# 1_PowerSupply.net
KiCad netlist of a schematic drawn in Altium Designer
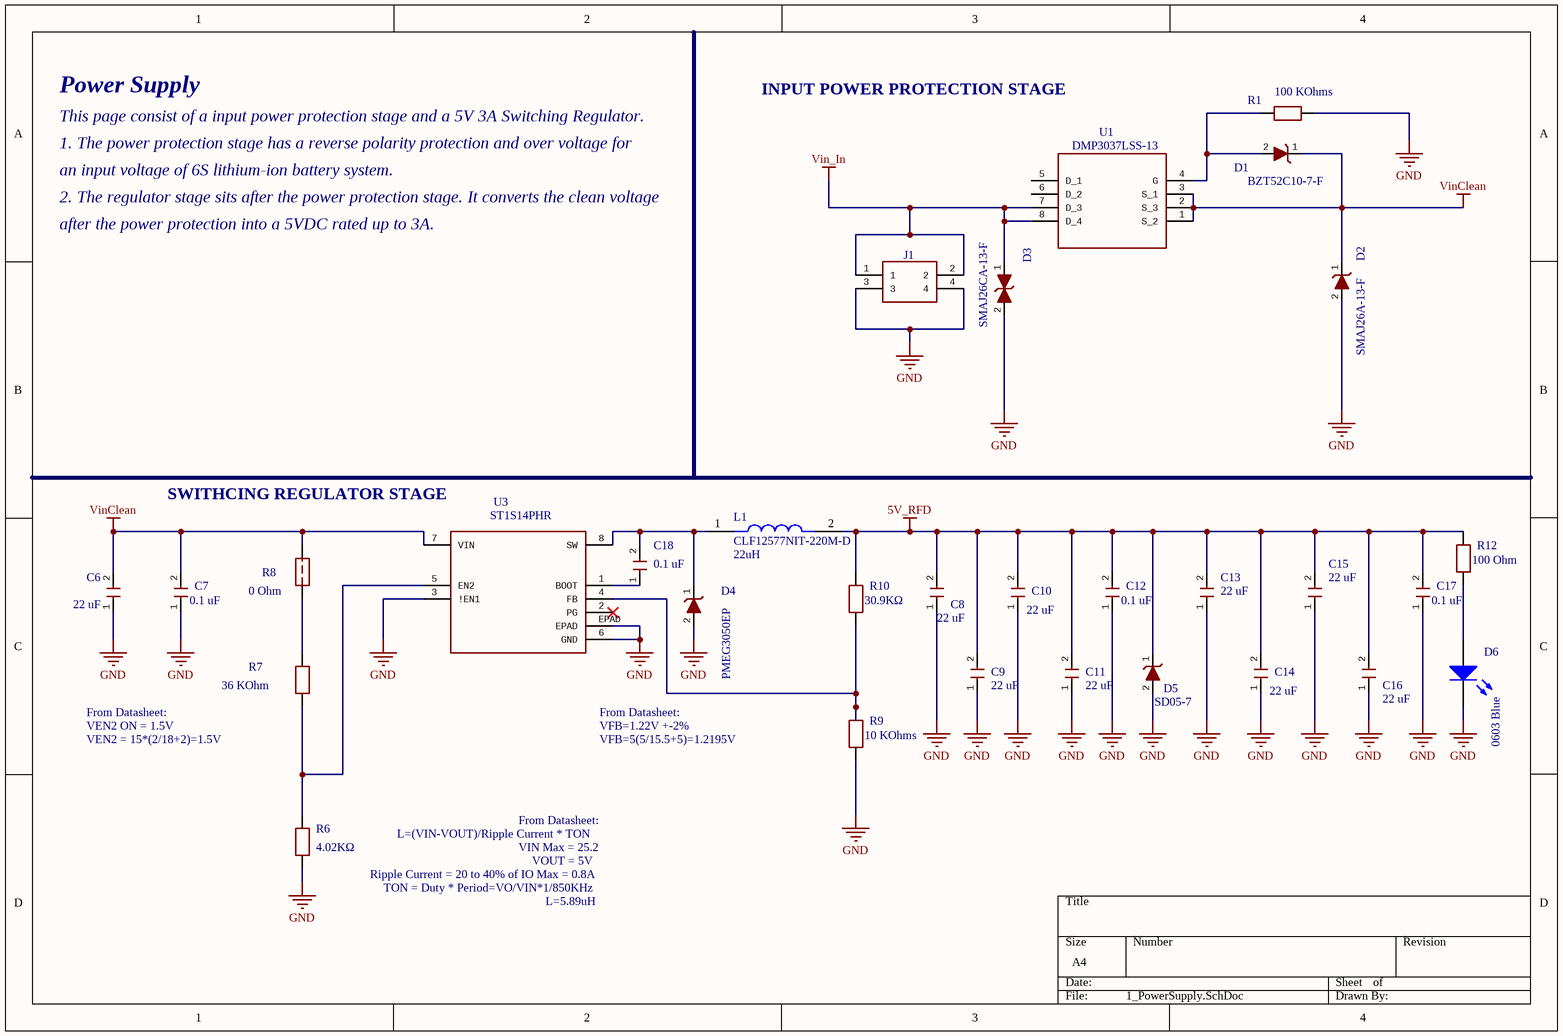
[diagram p0: 1_PowerSupply.SchDoc]

(export (version "E")
  (design (tool "Eeschema 10.0.6"))
  (components
    (comp (ref "C6")
      (value "22 uF")
      (footprint "CAP_0805")
      (description "Cap Ceramic 22uF 50V 0805")
      (fields (field (name "MANUFACTURER_PART_NUMBER") "C2012X5R1V226MT000E"))
      (libsource (lib "Passives") (part "C2012X5R1V226MT000E"))
    )
    (comp (ref "C7")
      (value "0.1 uF")
      (footprint "CAP_0603")
      (description "Cap Ceramic 0.1uF 50V 0603")
      (fields (field (name "PARTNUMBER") "CL10B104KB8NNNC"))
      (libsource (lib "Passives") (part "CL10B104KB8NNNC"))
    )
    (comp (ref "C8")
      (value "22 uF")
      (footprint "CAP_0805")
      (description "Cap Ceramic 22uF 50V 0805")
      (fields (field (name "MANUFACTURER_PART_NUMBER") "C2012X5R1V226MT000E"))
      (libsource (lib "Passives") (part "C2012X5R1V226MT000E"))
    )
    (comp (ref "C9")
      (value "22 uF")
      (footprint "CAP_0805")
      (description "Cap Ceramic 22uF 50V 0805")
      (fields (field (name "MANUFACTURER_PART_NUMBER") "C2012X5R1V226MT000E"))
      (libsource (lib "Passives") (part "C2012X5R1V226MT000E"))
    )
    (comp (ref "C10")
      (value "22 uF")
      (footprint "CAP_0805")
      (description "Cap Ceramic 22uF 50V 0805")
      (fields (field (name "MANUFACTURER_PART_NUMBER") "C2012X5R1V226MT000E"))
      (libsource (lib "Passives") (part "C2012X5R1V226MT000E"))
    )
    (comp (ref "C11")
      (value "22 uF")
      (footprint "CAP_0805")
      (description "Cap Ceramic 22uF 50V 0805")
      (fields (field (name "MANUFACTURER_PART_NUMBER") "C2012X5R1V226MT000E"))
      (libsource (lib "Passives") (part "C2012X5R1V226MT000E"))
    )
    (comp (ref "C12")
      (value "0.1 uF")
      (footprint "CAP_0603")
      (description "Cap Ceramic 0.1uF 50V 0603")
      (fields (field (name "PARTNUMBER") "CL10B104KB8NNNC"))
      (libsource (lib "Passives") (part "CL10B104KB8NNNC"))
    )
    (comp (ref "C13")
      (value "22 uF")
      (footprint "CAP_0805")
      (description "Cap Ceramic 22uF 50V 0805")
      (fields (field (name "MANUFACTURER_PART_NUMBER") "C2012X5R1V226MT000E"))
      (libsource (lib "Passives") (part "C2012X5R1V226MT000E"))
    )
    (comp (ref "C14")
      (value "22 uF")
      (footprint "CAP_0805")
      (description "Cap Ceramic 22uF 50V 0805")
      (fields (field (name "MANUFACTURER_PART_NUMBER") "C2012X5R1V226MT000E"))
      (libsource (lib "Passives") (part "C2012X5R1V226MT000E"))
    )
    (comp (ref "C15")
      (value "22 uF")
      (footprint "CAP_0805")
      (description "Cap Ceramic 22uF 50V 0805")
      (fields (field (name "MANUFACTURER_PART_NUMBER") "C2012X5R1V226MT000E"))
      (libsource (lib "Passives") (part "C2012X5R1V226MT000E"))
    )
    (comp (ref "C16")
      (value "22 uF")
      (footprint "CAP_0805")
      (description "Cap Ceramic 22uF 50V 0805")
      (fields (field (name "MANUFACTURER_PART_NUMBER") "C2012X5R1V226MT000E"))
      (libsource (lib "Passives") (part "C2012X5R1V226MT000E"))
    )
    (comp (ref "C17")
      (value "0.1 uF")
      (footprint "CAP_0603")
      (description "Cap Ceramic 0.1uF 50V 0603")
      (fields (field (name "PARTNUMBER") "CL10B104KB8NNNC"))
      (libsource (lib "Passives") (part "CL10B104KB8NNNC"))
    )
    (comp (ref "C18")
      (value "0.1 uF")
      (footprint "CAP_0603")
      (description "Cap Ceramic 0.1uF 50V 0603")
      (fields (field (name "PARTNUMBER") "CL10B104KB8NNNC"))
      (libsource (lib "Passives") (part "CL10B104KB8NNNC"))
    )
    (comp (ref "D1")
      (value "BZT52C10-7-F")
      (footprint "DIODE_SOD-123")
      (description "Diode Zener 10V 370mW")
      (fields (field (name "MOUSER_PART_NUMBER") "621-BZT52C10-F"))
      (libsource (lib "Passives") (part "BZT52C10-7-F"))
    )
    (comp (ref "D2")
      (value "SMAJ26A-13-F")
      (footprint "DIODE_DO-214AC")
      (description "Diode TVS 26V")
      (fields (field (name "COPYRIGHT") "Copyright (C) 2022 Ultra Librarian. All rights reserved."))
      (libsource (lib "Passives") (part "SMAJ26A-13-F"))
    )
    (comp (ref "D3")
      (value "SMAJ26CA-13-F")
      (footprint "DIODE_DO-214AC")
      (description "Diode TVS Bidirectional 26V")
      (fields (field (name "MANUFACTURER_PART_NUMBER") "SMAJ26A-13-F"))
      (libsource (lib "Passives") (part "SMAJ26CA-13-F"))
    )
    (comp (ref "D4")
      (value "PMEG3050EP")
      (footprint "DIODE_SOD-128")
      (description "Diode FastRecovery 30V SOD-128")
      (libsource (lib "Passives") (part "PMEG3050EP"))
    )
    (comp (ref "D5")
      (value "SD05-7")
      (footprint "DIODE_DO-214AC")
      (description "Diode TVS 5V")
      (libsource (lib "Passives") (part "SD05-7"))
    )
    (comp (ref "D6")
      (value "0603 Blue")
      (footprint "0603_LED_S1")
      (description "LED")
      (libsource (lib "Miscellaneous") (part "0603 LED Blue"))
    )
    (comp (ref "J1")
      (value "4 way r/a PCB header w/peg,Mini-Fit Jr Molex MINI-FIT JR. Series, Series Number 5569, 4.2mm Pitch 4 Way 2 Row Shrouded Right Angle PCB Header, Through Hole   Source:  Datasheet")
      (footprint "39-30-1040")
      (fields
        (field (name "MANUFACTURER_PART_NUMBER") "39-30-1040")
        (field (name "MOUSER_PART_NUMBER") "538-39-30-1040")
      )
      (libsource (lib "Connectors") (part "39-30-1040"))
    )
    (comp (ref "L1")
      (value "CLF12577NIT-220M-D")
      (footprint "IND_TDK_CLF12577NIT")
      (description "Ind 22uH Shielded Drum Core 4.5A")
      (fields (field (name "MANUFACTURER") "TDK") (field (name "ALTIUM_VALUE") "22uH"))
      (libsource (lib "Passives") (part "CLF12577NIT-220M-D"))
    )
    (comp (ref "R1")
      (value "100 KOhms")
      (footprint "RES_0805")
      (description "Res 100KOhms 1/2W 0805")
      (fields (field (name "PARTNUMBER") "ERJP06J104V"))
      (libsource (lib "Passives") (part "ERJP06J104V"))
    )
    (comp (ref "R6")
      (value "4.02KΩ")
      (footprint "RES_0603")
      (description "Res 4.02KOhm 1/10W 0603")
      (fields (field (name "PARTNUMBER") "ERJ3GEYJ200V") (field (name "Comment") "ERA3AEB4021V"))
      (libsource (lib "Passives") (part "ERA3AEB4021V"))
    )
    (comp (ref "R7")
      (value "36 KOhm")
      (footprint "RES_0603")
      (description "Res 36KOhm 1/10W 0603")
      (fields (field (name "PARTNUMBER") "ERJ3EKF3602V"))
      (libsource (lib "Passives") (part "ERJ3EKF3602V"))
    )
    (comp (ref "R8")
      (value "0 Ohm")
      (footprint "RES_0603")
      (description "Res 0Ohm 1/10W 0603")
      (fields (field (name "PARTNUMBER") "ERJ3GEY0R00V"))
      (libsource (lib "Passives") (part "ERJ3GEY0R00V"))
    )
    (comp (ref "R9")
      (value "10 KOhms")
      (footprint "RES_0603")
      (description "Res 10KOhms 1/10W 0603")
      (fields (field (name "PARTNUMBER") "ERJ3GEYJ103V"))
      (libsource (lib "Passives") (part "ERJ3GEYJ103V"))
    )
    (comp (ref "R10")
      (value "30.9KΩ")
      (footprint "RES_0603")
      (description "Res 30.9KOhm 1/10W 0603")
      (fields (field (name "PARTNUMBER") "CRCW060330K9FKEA"))
      (libsource (lib "Passives") (part "CRCW060330K9FKEA"))
    )
    (comp (ref "R12")
      (value "100 Ohm")
      (footprint "RES_0603")
      (description "Res 100Ohm 1/10W 0603")
      (fields (field (name "PARTNUMBER") "ERJU3RD1000V"))
      (libsource (lib "Passives") (part "ERJU3RD1000V"))
    )
    (comp (ref "U1")
      (value "DMP3037LSS-13")
      (footprint "MOSFET_SOIC-8_150mil")
      (description "P-Channel 30V 5.8A")
      (fields (field (name "PARTNUMBER") "Diodes Inc"))
      (libsource (lib "FETs") (part "DMP3037LSS-13"))
    )
    (comp (ref "U3")
      (value "ST1S14PHR")
      (footprint "REG_HSOP8")
      (description "Switching Step-down")
      (libsource (lib "Regulators") (part "ST1S14PHR"))
    )
  )
  (nets
    (net (code "1") (name "5V_RFD") (class "Default")
      (node (ref "C10") (pin "2") (pinfunction "2_2") (pintype "passive"))
      (node (ref "C11") (pin "2") (pinfunction "2_2") (pintype "passive"))
      (node (ref "C12") (pin "2") (pinfunction "2_2") (pintype "passive"))
      (node (ref "C13") (pin "2") (pinfunction "2_2") (pintype "passive"))
      (node (ref "C14") (pin "2") (pinfunction "2_2") (pintype "passive"))
      (node (ref "C15") (pin "2") (pinfunction "2_2") (pintype "passive"))
      (node (ref "C16") (pin "2") (pinfunction "2_2") (pintype "passive"))
      (node (ref "C17") (pin "2") (pinfunction "2_2") (pintype "passive"))
      (node (ref "C8") (pin "2") (pinfunction "2_2") (pintype "passive"))
      (node (ref "C9") (pin "2") (pinfunction "2_2") (pintype "passive"))
      (node (ref "D5") (pin "1") (pinfunction "1_1") (pintype "open_collector"))
      (node (ref "L1") (pin "2") (pinfunction "2_2") (pintype "passive"))
      (node (ref "R10") (pin "2") (pinfunction "2_2") (pintype "passive"))
      (node (ref "R12") (pin "2") (pinfunction "2_2") (pintype "passive"))
    )
    (net (code "2") (name "GND") (class "Default")
      (node (ref "C10") (pin "1") (pinfunction "1_1") (pintype "passive"))
      (node (ref "C11") (pin "1") (pinfunction "1_1") (pintype "passive"))
      (node (ref "C12") (pin "1") (pinfunction "1_1") (pintype "passive"))
      (node (ref "C13") (pin "1") (pinfunction "1_1") (pintype "passive"))
      (node (ref "C14") (pin "1") (pinfunction "1_1") (pintype "passive"))
      (node (ref "C15") (pin "1") (pinfunction "1_1") (pintype "passive"))
      (node (ref "C16") (pin "1") (pinfunction "1_1") (pintype "passive"))
      (node (ref "C17") (pin "1") (pinfunction "1_1") (pintype "passive"))
      (node (ref "C6") (pin "1") (pinfunction "1_1") (pintype "passive"))
      (node (ref "C7") (pin "1") (pinfunction "1_1") (pintype "passive"))
      (node (ref "C8") (pin "1") (pinfunction "1_1") (pintype "passive"))
      (node (ref "C9") (pin "1") (pinfunction "1_1") (pintype "passive"))
      (node (ref "D2") (pin "2") (pinfunction "2_2") (pintype "open_collector"))
      (node (ref "D3") (pin "2") (pinfunction "2_2") (pintype "passive"))
      (node (ref "D4") (pin "2") (pinfunction "2_2") (pintype "passive"))
      (node (ref "D5") (pin "2") (pinfunction "2_2") (pintype "open_collector"))
      (node (ref "D6") (pin "K") (pinfunction "K_K") (pintype "passive"))
      (node (ref "J1") (pin "3") (pinfunction "3_3") (pintype "passive"))
      (node (ref "J1") (pin "4") (pinfunction "4_4") (pintype "passive"))
      (node (ref "R1") (pin "2") (pinfunction "2_2") (pintype "passive"))
      (node (ref "R6") (pin "1") (pinfunction "1_1") (pintype "passive"))
      (node (ref "R9") (pin "1") (pinfunction "1_1") (pintype "passive"))
      (node (ref "U3") (pin "3") (pinfunction "!EN1_3") (pintype "passive"))
      (node (ref "U3") (pin "6") (pinfunction "GND_6") (pintype "passive"))
      (node (ref "U3") (pin "EPAD") (pinfunction "EPAD_EPAD") (pintype "passive"))
    )
    (net (code "3") (name "Net-(D6-PadA)") (class "Default")
      (node (ref "D6") (pin "A") (pinfunction "A_A") (pintype "passive"))
      (node (ref "R12") (pin "1") (pinfunction "1_1") (pintype "passive"))
    )
    (net (code "4") (name "Net-(R7-Pad2)") (class "Default")
      (node (ref "R7") (pin "2") (pinfunction "2_2") (pintype "passive"))
      (node (ref "R8") (pin "1") (pinfunction "1_1") (pintype "passive"))
    )
    (net (code "5") (name "Net-(U1-G)") (class "Default")
      (node (ref "D1") (pin "2") (pinfunction "2_2") (pintype "open_collector"))
      (node (ref "R1") (pin "1") (pinfunction "1_1") (pintype "passive"))
      (node (ref "U1") (pin "4") (pinfunction "G_4") (pintype "passive"))
    )
    (net (code "6") (name "Net-(U3-BOOT)") (class "Default")
      (node (ref "C18") (pin "1") (pinfunction "1_1") (pintype "passive"))
      (node (ref "U3") (pin "1") (pinfunction "BOOT_1") (pintype "passive"))
    )
    (net (code "7") (name "Net-(U3-EN2)") (class "Default")
      (node (ref "R6") (pin "2") (pinfunction "2_2") (pintype "passive"))
      (node (ref "R7") (pin "1") (pinfunction "1_1") (pintype "passive"))
      (node (ref "U3") (pin "5") (pinfunction "EN2_5") (pintype "passive"))
    )
    (net (code "8") (name "Net-(U3-FB)") (class "Default")
      (node (ref "R10") (pin "1") (pinfunction "1_1") (pintype "passive"))
      (node (ref "R9") (pin "2") (pinfunction "2_2") (pintype "passive"))
      (node (ref "U3") (pin "4") (pinfunction "FB_4") (pintype "passive"))
    )
    (net (code "9") (name "Net-(U3-SW)") (class "Default")
      (node (ref "C18") (pin "2") (pinfunction "2_2") (pintype "passive"))
      (node (ref "D4") (pin "1") (pinfunction "1_1") (pintype "passive"))
      (node (ref "L1") (pin "1") (pinfunction "1_1") (pintype "passive"))
      (node (ref "U3") (pin "8") (pinfunction "SW_8") (pintype "passive"))
    )
    (net (code "10") (name "VinClean") (class "Default")
      (node (ref "C6") (pin "2") (pinfunction "2_2") (pintype "passive"))
      (node (ref "C7") (pin "2") (pinfunction "2_2") (pintype "passive"))
      (node (ref "D1") (pin "1") (pinfunction "1_1") (pintype "open_collector"))
      (node (ref "D2") (pin "1") (pinfunction "1_1") (pintype "open_collector"))
      (node (ref "R8") (pin "2") (pinfunction "2_2") (pintype "passive"))
      (node (ref "U1") (pin "1") (pinfunction "S_2_1") (pintype "passive"))
      (node (ref "U1") (pin "2") (pinfunction "S_3_2") (pintype "passive"))
      (node (ref "U1") (pin "3") (pinfunction "S_1_3") (pintype "passive"))
      (node (ref "U3") (pin "7") (pinfunction "VIN_7") (pintype "power_in"))
    )
    (net (code "11") (name "Vin_In") (class "Default")
      (node (ref "D3") (pin "1") (pinfunction "1_1") (pintype "passive"))
      (node (ref "J1") (pin "1") (pinfunction "1_1") (pintype "passive"))
      (node (ref "J1") (pin "2") (pinfunction "2_2") (pintype "passive"))
      (node (ref "U1") (pin "7") (pinfunction "D_3_7") (pintype "passive"))
      (node (ref "U1") (pin "8") (pinfunction "D_4_8") (pintype "passive"))
    )
    (net (code "12") (name "unconnected-(U1-D_1-Pad5)") (class "Default")
      (node (ref "U1") (pin "5") (pinfunction "D_1_5") (pintype "passive"))
    )
    (net (code "13") (name "unconnected-(U1-D_2-Pad6)") (class "Default")
      (node (ref "U1") (pin "6") (pinfunction "D_2_6") (pintype "passive"))
    )
    (net (code "14") (name "unconnected-(U3-PG-Pad2)") (class "Default")
      (node (ref "U3") (pin "2") (pinfunction "PG_2") (pintype "passive+no_connect"))
    )
  )
)
